# board.net
KiCad netlist of a schematic drawn in EAGLE
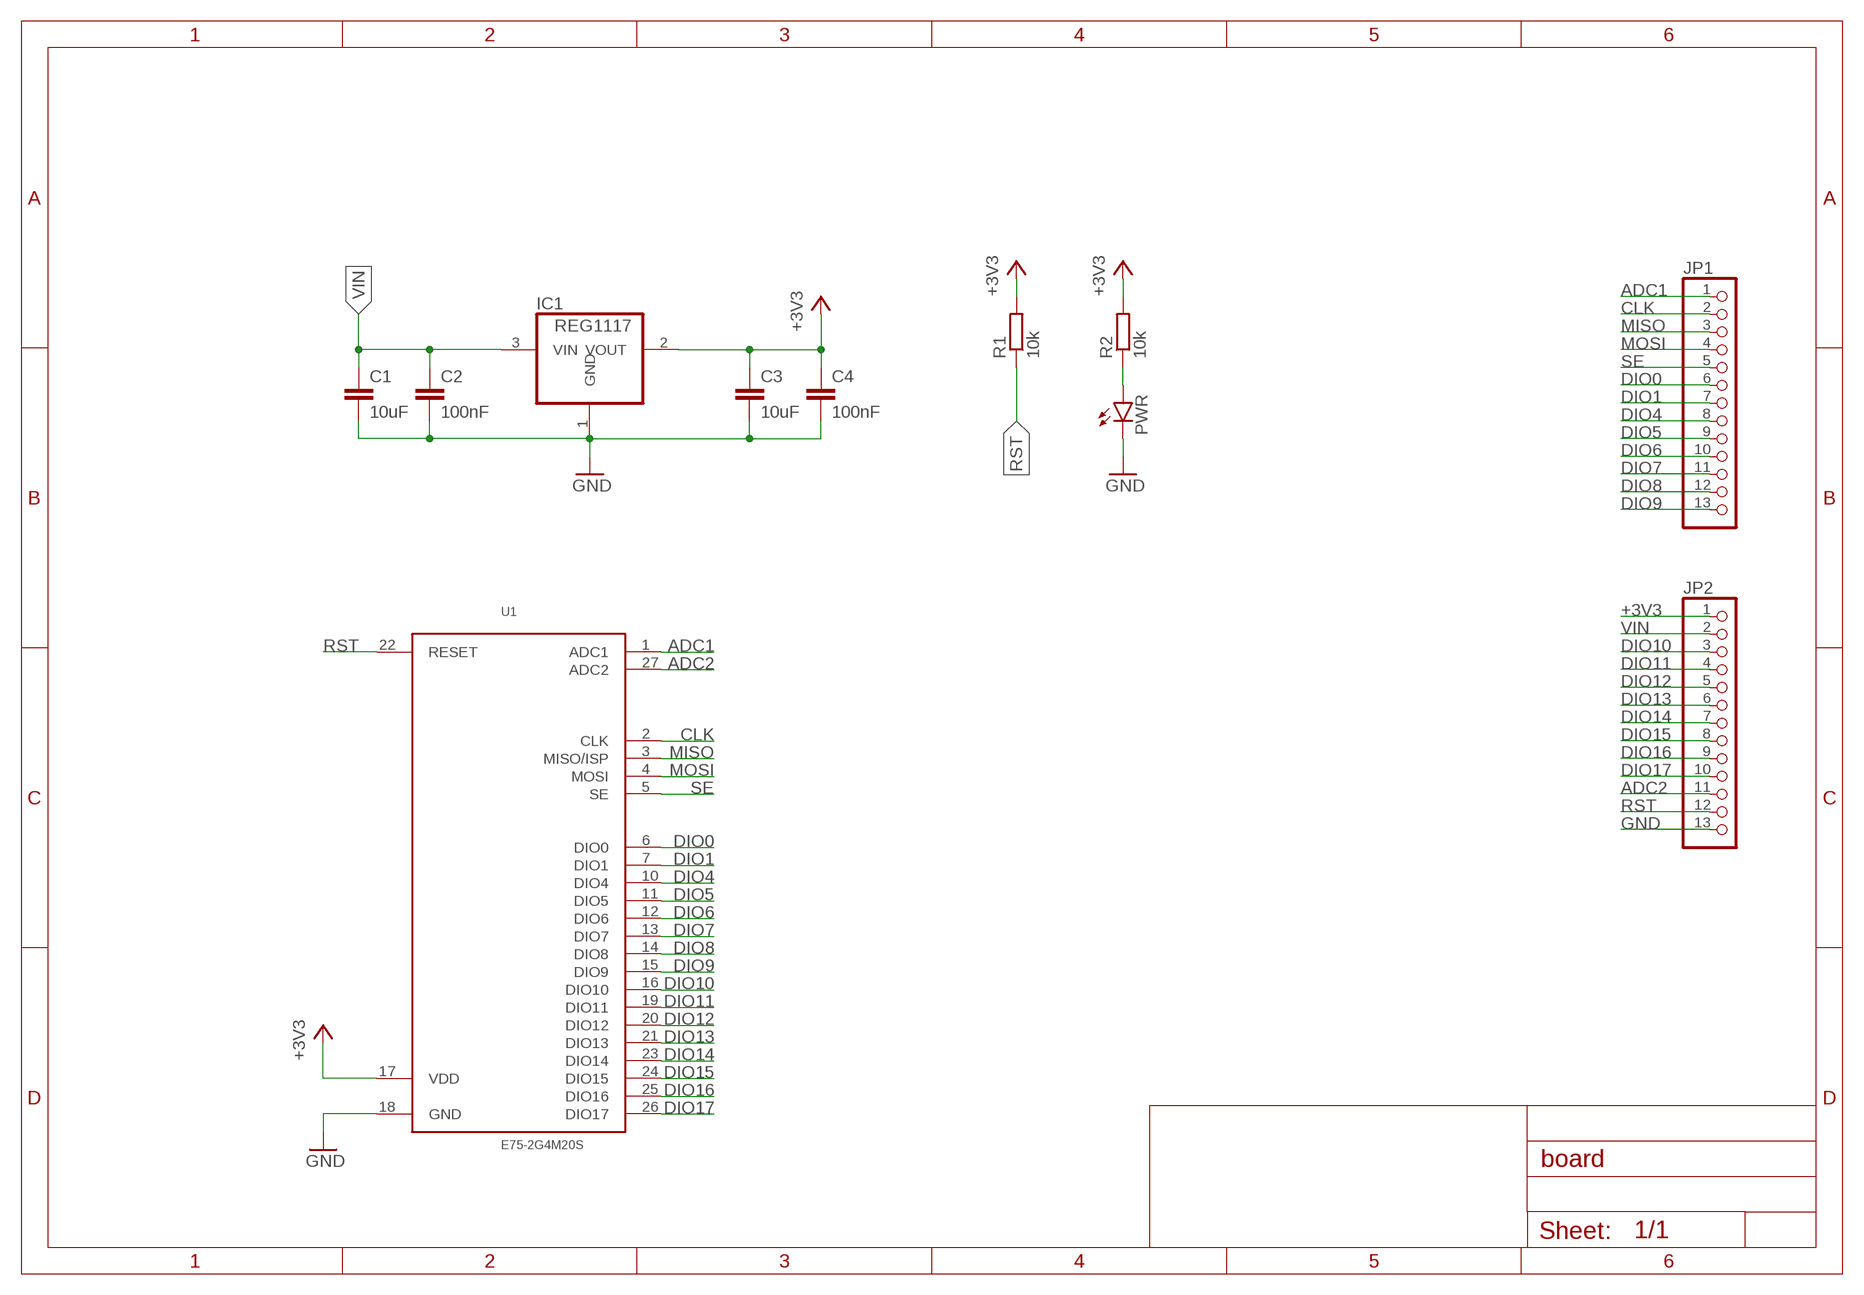
[diagram p0: schematic, sheet 1]

(export (version "E")
  (design (tool "Eeschema 10.0.6"))
  (components
    (comp (ref "C1")
      (value "10uF")
      (footprint "eagle-import:C0603")
      (libsource (lib "eagle-import") (part "C-EUC0603"))
    )
    (comp (ref "C2")
      (value "100nF")
      (footprint "eagle-import:C0603")
      (libsource (lib "eagle-import") (part "C-EUC0603"))
    )
    (comp (ref "C3")
      (value "10uF")
      (footprint "eagle-import:C0603")
      (libsource (lib "eagle-import") (part "C-EUC0603"))
    )
    (comp (ref "C4")
      (value "100nF")
      (footprint "eagle-import:C0603")
      (libsource (lib "eagle-import") (part "C-EUC0603"))
    )
    (comp (ref "IC1")
      (value "REG1117")
      (footprint "eagle-import:SOT223")
      (libsource (lib "eagle-import") (part "REG1117"))
    )
    (comp (ref "JP1")
      (value "PINHD-1X13")
      (footprint "eagle-import:1X13")
      (libsource (lib "eagle-import") (part "PINHD-1X13"))
    )
    (comp (ref "JP2")
      (value "PINHD-1X13")
      (footprint "eagle-import:1X13")
      (libsource (lib "eagle-import") (part "PINHD-1X13"))
    )
    (comp (ref "PWR")
      (value "LEDSML0603")
      (footprint "eagle-import:SML0603")
      (libsource (lib "eagle-import") (part "LEDSML0603"))
    )
    (comp (ref "R1")
      (value "10k")
      (footprint "eagle-import:R0603")
      (libsource (lib "eagle-import") (part "R-EU_R0603"))
    )
    (comp (ref "R2")
      (value "10k")
      (footprint "eagle-import:R0603")
      (libsource (lib "eagle-import") (part "R-EU_R0603"))
    )
    (comp (ref "U1")
      (value "E75-2G4M20S")
      (footprint "eagle-import:E75-2G4M20S")
      (libsource (lib "eagle-import") (part "E75-2G4M20S"))
    )
  )
  (nets
    (net (code "1") (name "+3V3") (class "Default")
      (node (ref "C3") (pin "1") (pinfunction "1_1") (pintype "passive"))
      (node (ref "C4") (pin "1") (pinfunction "1_1") (pintype "passive"))
      (node (ref "IC1") (pin "2") (pinfunction "VOUT_2") (pintype "output"))
      (node (ref "JP2") (pin "1") (pinfunction "1_1") (pintype "passive"))
      (node (ref "R1") (pin "2") (pinfunction "2_2") (pintype "passive"))
      (node (ref "R2") (pin "2") (pinfunction "2_2") (pintype "passive"))
      (node (ref "U1") (pin "17") (pinfunction "VDD_17") (pintype "bidirectional"))
    )
    (net (code "2") (name "/ADC1") (class "Default")
      (node (ref "JP1") (pin "1") (pinfunction "1_1") (pintype "passive"))
      (node (ref "U1") (pin "1") (pinfunction "ADC1_1") (pintype "bidirectional"))
    )
    (net (code "3") (name "/ADC2") (class "Default")
      (node (ref "JP2") (pin "11") (pinfunction "11_11") (pintype "passive"))
      (node (ref "U1") (pin "27") (pinfunction "ADC2_27") (pintype "bidirectional"))
    )
    (net (code "4") (name "/CLK") (class "Default")
      (node (ref "JP1") (pin "2") (pinfunction "2_2") (pintype "passive"))
      (node (ref "U1") (pin "2") (pinfunction "CLK_2") (pintype "bidirectional"))
    )
    (net (code "5") (name "/DIO0") (class "Default")
      (node (ref "JP1") (pin "6") (pinfunction "6_6") (pintype "passive"))
      (node (ref "U1") (pin "6") (pinfunction "DIO0_6") (pintype "bidirectional"))
    )
    (net (code "6") (name "/DIO1") (class "Default")
      (node (ref "JP1") (pin "7") (pinfunction "7_7") (pintype "passive"))
      (node (ref "U1") (pin "7") (pinfunction "DIO1_7") (pintype "bidirectional"))
    )
    (net (code "7") (name "/DIO4") (class "Default")
      (node (ref "JP1") (pin "8") (pinfunction "8_8") (pintype "passive"))
      (node (ref "U1") (pin "10") (pinfunction "DIO4_10") (pintype "bidirectional"))
    )
    (net (code "8") (name "/DIO5") (class "Default")
      (node (ref "JP1") (pin "9") (pinfunction "9_9") (pintype "passive"))
      (node (ref "U1") (pin "11") (pinfunction "DIO5_11") (pintype "bidirectional"))
    )
    (net (code "9") (name "/DIO6") (class "Default")
      (node (ref "JP1") (pin "10") (pinfunction "10_10") (pintype "passive"))
      (node (ref "U1") (pin "12") (pinfunction "DIO6_12") (pintype "bidirectional"))
    )
    (net (code "10") (name "/DIO7") (class "Default")
      (node (ref "JP1") (pin "11") (pinfunction "11_11") (pintype "passive"))
      (node (ref "U1") (pin "13") (pinfunction "DIO7_13") (pintype "bidirectional"))
    )
    (net (code "11") (name "/DIO8") (class "Default")
      (node (ref "JP1") (pin "12") (pinfunction "12_12") (pintype "passive"))
      (node (ref "U1") (pin "14") (pinfunction "DIO8_14") (pintype "bidirectional"))
    )
    (net (code "12") (name "/DIO9") (class "Default")
      (node (ref "JP1") (pin "13") (pinfunction "13_13") (pintype "passive"))
      (node (ref "U1") (pin "15") (pinfunction "DIO9_15") (pintype "bidirectional"))
    )
    (net (code "13") (name "/DIO10") (class "Default")
      (node (ref "JP2") (pin "3") (pinfunction "3_3") (pintype "passive"))
      (node (ref "U1") (pin "16") (pinfunction "DIO10_16") (pintype "bidirectional"))
    )
    (net (code "14") (name "/DIO11") (class "Default")
      (node (ref "JP2") (pin "4") (pinfunction "4_4") (pintype "passive"))
      (node (ref "U1") (pin "19") (pinfunction "DIO11_19") (pintype "bidirectional"))
    )
    (net (code "15") (name "/DIO12") (class "Default")
      (node (ref "JP2") (pin "5") (pinfunction "5_5") (pintype "passive"))
      (node (ref "U1") (pin "20") (pinfunction "DIO12_20") (pintype "bidirectional"))
    )
    (net (code "16") (name "/DIO13") (class "Default")
      (node (ref "JP2") (pin "6") (pinfunction "6_6") (pintype "passive"))
      (node (ref "U1") (pin "21") (pinfunction "DIO13_21") (pintype "bidirectional"))
    )
    (net (code "17") (name "/DIO14") (class "Default")
      (node (ref "JP2") (pin "7") (pinfunction "7_7") (pintype "passive"))
      (node (ref "U1") (pin "23") (pinfunction "DIO14_23") (pintype "bidirectional"))
    )
    (net (code "18") (name "/DIO15") (class "Default")
      (node (ref "JP2") (pin "8") (pinfunction "8_8") (pintype "passive"))
      (node (ref "U1") (pin "24") (pinfunction "DIO15_24") (pintype "bidirectional"))
    )
    (net (code "19") (name "/DIO16") (class "Default")
      (node (ref "JP2") (pin "9") (pinfunction "9_9") (pintype "passive"))
      (node (ref "U1") (pin "25") (pinfunction "DIO16_25") (pintype "bidirectional"))
    )
    (net (code "20") (name "/DIO17") (class "Default")
      (node (ref "JP2") (pin "10") (pinfunction "10_10") (pintype "passive"))
      (node (ref "U1") (pin "26") (pinfunction "DIO17_26") (pintype "bidirectional"))
    )
    (net (code "21") (name "/MISO") (class "Default")
      (node (ref "JP1") (pin "3") (pinfunction "3_3") (pintype "passive"))
      (node (ref "U1") (pin "3") (pinfunction "MISO/ISP_3") (pintype "bidirectional"))
    )
    (net (code "22") (name "/MOSI") (class "Default")
      (node (ref "JP1") (pin "4") (pinfunction "4_4") (pintype "passive"))
      (node (ref "U1") (pin "4") (pinfunction "MOSI_4") (pintype "bidirectional"))
    )
    (net (code "23") (name "/SE") (class "Default")
      (node (ref "JP1") (pin "5") (pinfunction "5_5") (pintype "passive"))
      (node (ref "U1") (pin "5") (pinfunction "SE_5") (pintype "bidirectional"))
    )
    (net (code "24") (name "GND") (class "Default")
      (node (ref "C1") (pin "2") (pinfunction "2_2") (pintype "passive"))
      (node (ref "C2") (pin "2") (pinfunction "2_2") (pintype "passive"))
      (node (ref "C3") (pin "2") (pinfunction "2_2") (pintype "passive"))
      (node (ref "C4") (pin "2") (pinfunction "2_2") (pintype "passive"))
      (node (ref "IC1") (pin "1") (pinfunction "GND_1") (pintype "power_in"))
      (node (ref "JP2") (pin "13") (pinfunction "13_13") (pintype "passive"))
      (node (ref "PWR") (pin "C") (pinfunction "C_C") (pintype "passive"))
      (node (ref "U1") (pin "18") (pinfunction "GND_18") (pintype "bidirectional"))
    )
    (net (code "25") (name "Net-(PWR-PadA)") (class "Default")
      (node (ref "PWR") (pin "A") (pinfunction "A_A") (pintype "passive"))
      (node (ref "R2") (pin "1") (pinfunction "1_1") (pintype "passive"))
    )
    (net (code "26") (name "RST") (class "Default")
      (node (ref "JP2") (pin "12") (pinfunction "12_12") (pintype "passive"))
      (node (ref "R1") (pin "1") (pinfunction "1_1") (pintype "passive"))
      (node (ref "U1") (pin "22") (pinfunction "RESET_22") (pintype "bidirectional"))
    )
    (net (code "27") (name "VIN") (class "Default")
      (node (ref "C1") (pin "1") (pinfunction "1_1") (pintype "passive"))
      (node (ref "C2") (pin "1") (pinfunction "1_1") (pintype "passive"))
      (node (ref "IC1") (pin "3") (pinfunction "VIN_3") (pintype "input"))
      (node (ref "JP2") (pin "2") (pinfunction "2_2") (pintype "passive"))
    )
  )
)
